# 003_Serial_Port.net
KiCad netlist of a schematic drawn in Altium Designer
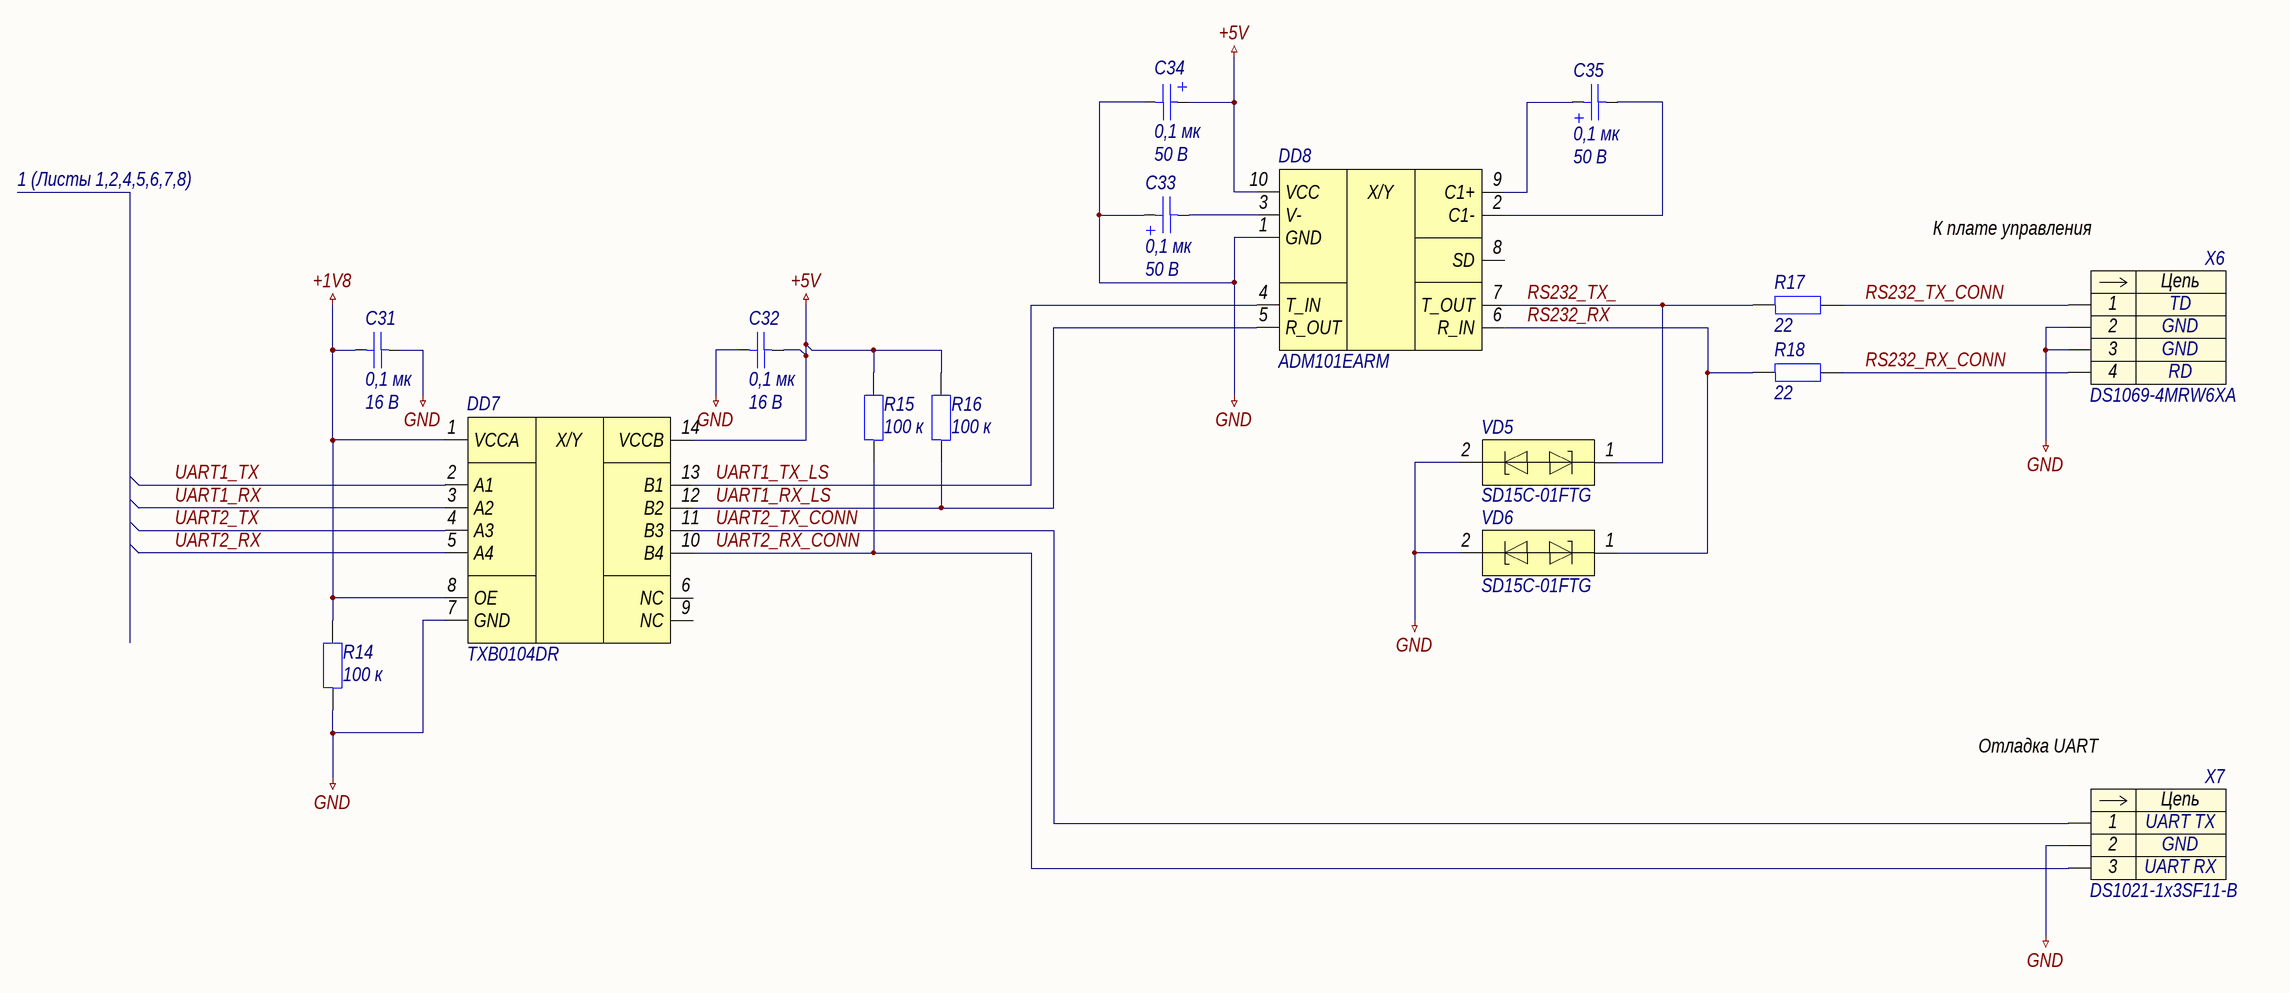
[diagram p0: 003_Serial_Port.SchDoc]

(export (version "E")
  (design (tool "Eeschema 10.0.6"))
  (components
    (comp (ref "C31")
      (value "0,1 мк")
      (footprint "C0603")
      (description "=Описание")
      (fields (field (name "НАПРЯЖЕНИЕ") "16 В"))
      (libsource (lib "Database_Students") (part "CAPACITOR-NONPOLAR"))
    )
    (comp (ref "C32")
      (value "0,1 мк")
      (footprint "C0603")
      (description "=Описание")
      (fields (field (name "НАПРЯЖЕНИЕ") "16 В"))
      (libsource (lib "Database_Students") (part "CAPACITOR-NONPOLAR"))
    )
    (comp (ref "C33")
      (value "0,1 мк")
      (footprint "C3216-18")
      (description "=Описание")
      (fields (field (name "НАПРЯЖЕНИЕ") "50 В"))
      (libsource (lib "Database_Students") (part "CAPACITOR-POLAR"))
    )
    (comp (ref "C34")
      (value "0,1 мк")
      (footprint "C3216-18")
      (description "=Описание")
      (fields (field (name "НАПРЯЖЕНИЕ") "50 В"))
      (libsource (lib "Database_Students") (part "CAPACITOR-POLAR"))
    )
    (comp (ref "C35")
      (value "0,1 мк")
      (footprint "C3216-18")
      (description "=Описание")
      (fields (field (name "НАПРЯЖЕНИЕ") "50 В"))
      (libsource (lib "Database_Students") (part "CAPACITOR-POLAR"))
    )
    (comp (ref "DD7")
      (value "TXB0104DR")
      (footprint "SOIC-14-P127-865X390X175-L84X41")
      (description "=Описание")
      (libsource (lib "Database_Students") (part "TXB0104DR"))
    )
    (comp (ref "DD8")
      (value "ADM101EARM")
      (footprint "MSOP-10-P50-300X300X110-L55X23")
      (description "=Описание")
      (libsource (lib "Database_Students") (part "ADM101EARM"))
    )
    (comp (ref "R14")
      (value "100 к")
      (footprint "R0603")
      (description "=Описание")
      (libsource (lib "Database_Students") (part "RESISTOR-COMMON"))
    )
    (comp (ref "R15")
      (value "100 к")
      (footprint "R0603")
      (description "=Описание")
      (libsource (lib "Database_Students") (part "RESISTOR-COMMON"))
    )
    (comp (ref "R16")
      (value "100 к")
      (footprint "R0603")
      (description "=Описание")
      (libsource (lib "Database_Students") (part "RESISTOR-COMMON"))
    )
    (comp (ref "R17")
      (value "22")
      (footprint "R0603")
      (description "=Описание")
      (libsource (lib "Database_Students") (part "RESISTOR-COMMON"))
    )
    (comp (ref "R18")
      (value "22")
      (footprint "R0603")
      (description "=Описание")
      (libsource (lib "Database_Students") (part "RESISTOR-COMMON"))
    )
    (comp (ref "VD5")
      (value "SD15C-01FTG")
      (footprint "SOD-323-257X130X114")
      (description "=Описание")
      (libsource (lib "Database_Students") (part "ZENER-BI-DIRECTIONAL"))
    )
    (comp (ref "VD6")
      (value "SD15C-01FTG")
      (footprint "SOD-323-257X130X114")
      (description "=Описание")
      (libsource (lib "Database_Students") (part "ZENER-BI-DIRECTIONAL"))
    )
    (comp (ref "X6")
      (value "DS1069-4MRW6XA")
      (footprint "DS1069-4MRW6XA")
      (description "=Описание")
      (libsource (lib "Database_Students") (part "HEADER-4-PLG"))
    )
    (comp (ref "X7")
      (value "DS1021-1x3SF11-B")
      (footprint "DS1021-1X3SF11-B")
      (description "=Описание")
      (libsource (lib "Database_Students") (part "HEADER-3-PLG"))
    )
  )
  (nets
    (net (code "1") (name "+1V8") (class "Default")
      (node (ref "C31") (pin "1") (pinfunction "1_1") (pintype "passive"))
      (node (ref "DD7") (pin "1") (pinfunction "VCCA_1") (pintype "passive"))
      (node (ref "DD7") (pin "8") (pinfunction "OE_8") (pintype "passive"))
      (node (ref "R14") (pin "2") (pinfunction "2_2") (pintype "passive"))
    )
    (net (code "2") (name "+5V") (class "Default")
      (node (ref "C32") (pin "2") (pinfunction "2_2") (pintype "passive"))
      (node (ref "C34") (pin "1") (pinfunction "1_1") (pintype "passive"))
      (node (ref "DD7") (pin "14") (pinfunction "VCCB_14") (pintype "passive"))
      (node (ref "DD8") (pin "10") (pinfunction "VCC_10") (pintype "passive"))
      (node (ref "R15") (pin "2") (pinfunction "2_2") (pintype "passive"))
      (node (ref "R16") (pin "2") (pinfunction "2_2") (pintype "passive"))
    )
    (net (code "3") (name "/RS232_RX") (class "Default")
      (node (ref "DD8") (pin "6") (pinfunction "R_IN_6") (pintype "passive"))
      (node (ref "R18") (pin "1") (pinfunction "1_1") (pintype "passive"))
      (node (ref "VD6") (pin "1") (pinfunction "1_1") (pintype "passive"))
    )
    (net (code "4") (name "/RS232_RX_CONN") (class "Default")
      (node (ref "R18") (pin "2") (pinfunction "2_2") (pintype "passive"))
      (node (ref "X6") (pin "4") (pinfunction "4_4") (pintype "passive"))
    )
    (net (code "5") (name "/RS232_TX_") (class "Default")
      (node (ref "DD8") (pin "7") (pinfunction "T_OUT_7") (pintype "passive"))
      (node (ref "R17") (pin "1") (pinfunction "1_1") (pintype "passive"))
      (node (ref "VD5") (pin "1") (pinfunction "1_1") (pintype "passive"))
    )
    (net (code "6") (name "/RS232_TX_CONN") (class "Default")
      (node (ref "R17") (pin "2") (pinfunction "2_2") (pintype "passive"))
      (node (ref "X6") (pin "1") (pinfunction "1_1") (pintype "passive"))
    )
    (net (code "7") (name "/UART1_RX") (class "Default")
      (node (ref "DD7") (pin "3") (pinfunction "A2_3") (pintype "passive"))
    )
    (net (code "8") (name "/UART1_RX_LS") (class "Default")
      (node (ref "DD7") (pin "12") (pinfunction "B2_12") (pintype "passive"))
      (node (ref "DD8") (pin "5") (pinfunction "R_OUT_5") (pintype "passive"))
      (node (ref "R16") (pin "1") (pinfunction "1_1") (pintype "passive"))
    )
    (net (code "9") (name "/UART1_TX") (class "Default")
      (node (ref "DD7") (pin "2") (pinfunction "A1_2") (pintype "passive"))
    )
    (net (code "10") (name "/UART1_TX_LS") (class "Default")
      (node (ref "DD7") (pin "13") (pinfunction "B1_13") (pintype "passive"))
      (node (ref "DD8") (pin "4") (pinfunction "T_IN_4") (pintype "passive"))
    )
    (net (code "11") (name "/UART2_RX") (class "Default")
      (node (ref "DD7") (pin "5") (pinfunction "A4_5") (pintype "passive"))
    )
    (net (code "12") (name "/UART2_RX_CONN") (class "Default")
      (node (ref "DD7") (pin "10") (pinfunction "B4_10") (pintype "passive"))
      (node (ref "R15") (pin "1") (pinfunction "1_1") (pintype "passive"))
      (node (ref "X7") (pin "3") (pinfunction "3_3") (pintype "passive"))
    )
    (net (code "13") (name "/UART2_TX") (class "Default")
      (node (ref "DD7") (pin "4") (pinfunction "A3_4") (pintype "passive"))
    )
    (net (code "14") (name "/UART2_TX_CONN") (class "Default")
      (node (ref "DD7") (pin "11") (pinfunction "B3_11") (pintype "passive"))
      (node (ref "X7") (pin "1") (pinfunction "1_1") (pintype "passive"))
    )
    (net (code "15") (name "GND") (class "Default")
      (node (ref "C31") (pin "2") (pinfunction "2_2") (pintype "passive"))
      (node (ref "C32") (pin "1") (pinfunction "1_1") (pintype "passive"))
      (node (ref "C33") (pin "1") (pinfunction "1_1") (pintype "passive"))
      (node (ref "C34") (pin "2") (pinfunction "2_2") (pintype "passive"))
      (node (ref "DD7") (pin "7") (pinfunction "GND_7") (pintype "passive"))
      (node (ref "DD8") (pin "1") (pinfunction "GND_1") (pintype "passive"))
      (node (ref "R14") (pin "1") (pinfunction "1_1") (pintype "passive"))
      (node (ref "VD5") (pin "2") (pinfunction "2_2") (pintype "passive"))
      (node (ref "VD6") (pin "2") (pinfunction "2_2") (pintype "passive"))
      (node (ref "X6") (pin "2") (pinfunction "2_2") (pintype "passive"))
      (node (ref "X6") (pin "3") (pinfunction "3_3") (pintype "passive"))
      (node (ref "X7") (pin "2") (pinfunction "2_2") (pintype "passive"))
    )
    (net (code "16") (name "Net-(DD8-C1+)") (class "Default")
      (node (ref "C35") (pin "1") (pinfunction "1_1") (pintype "passive"))
      (node (ref "DD8") (pin "9") (pinfunction "C1+_9") (pintype "passive"))
    )
    (net (code "17") (name "Net-(DD8-C1-)") (class "Default")
      (node (ref "C35") (pin "2") (pinfunction "2_2") (pintype "passive"))
      (node (ref "DD8") (pin "2") (pinfunction "C1-_2") (pintype "passive"))
    )
    (net (code "18") (name "Net-(DD8-V-)") (class "Default")
      (node (ref "C33") (pin "2") (pinfunction "2_2") (pintype "passive"))
      (node (ref "DD8") (pin "3") (pinfunction "V-_3") (pintype "passive"))
    )
    (net (code "19") (name "unconnected-(DD7-NC-Pad6)") (class "Default")
      (node (ref "DD7") (pin "6") (pinfunction "NC_6") (pintype "passive"))
    )
    (net (code "20") (name "unconnected-(DD7-NC-Pad9)") (class "Default")
      (node (ref "DD7") (pin "9") (pinfunction "NC_9") (pintype "passive"))
    )
    (net (code "21") (name "unconnected-(DD8-SD-Pad8)") (class "Default")
      (node (ref "DD8") (pin "8") (pinfunction "SD_8") (pintype "passive"))
    )
  )
)
